# OpenPMU_BBB_Cape_V2_3.net
KiCad netlist of a schematic drawn in EAGLE
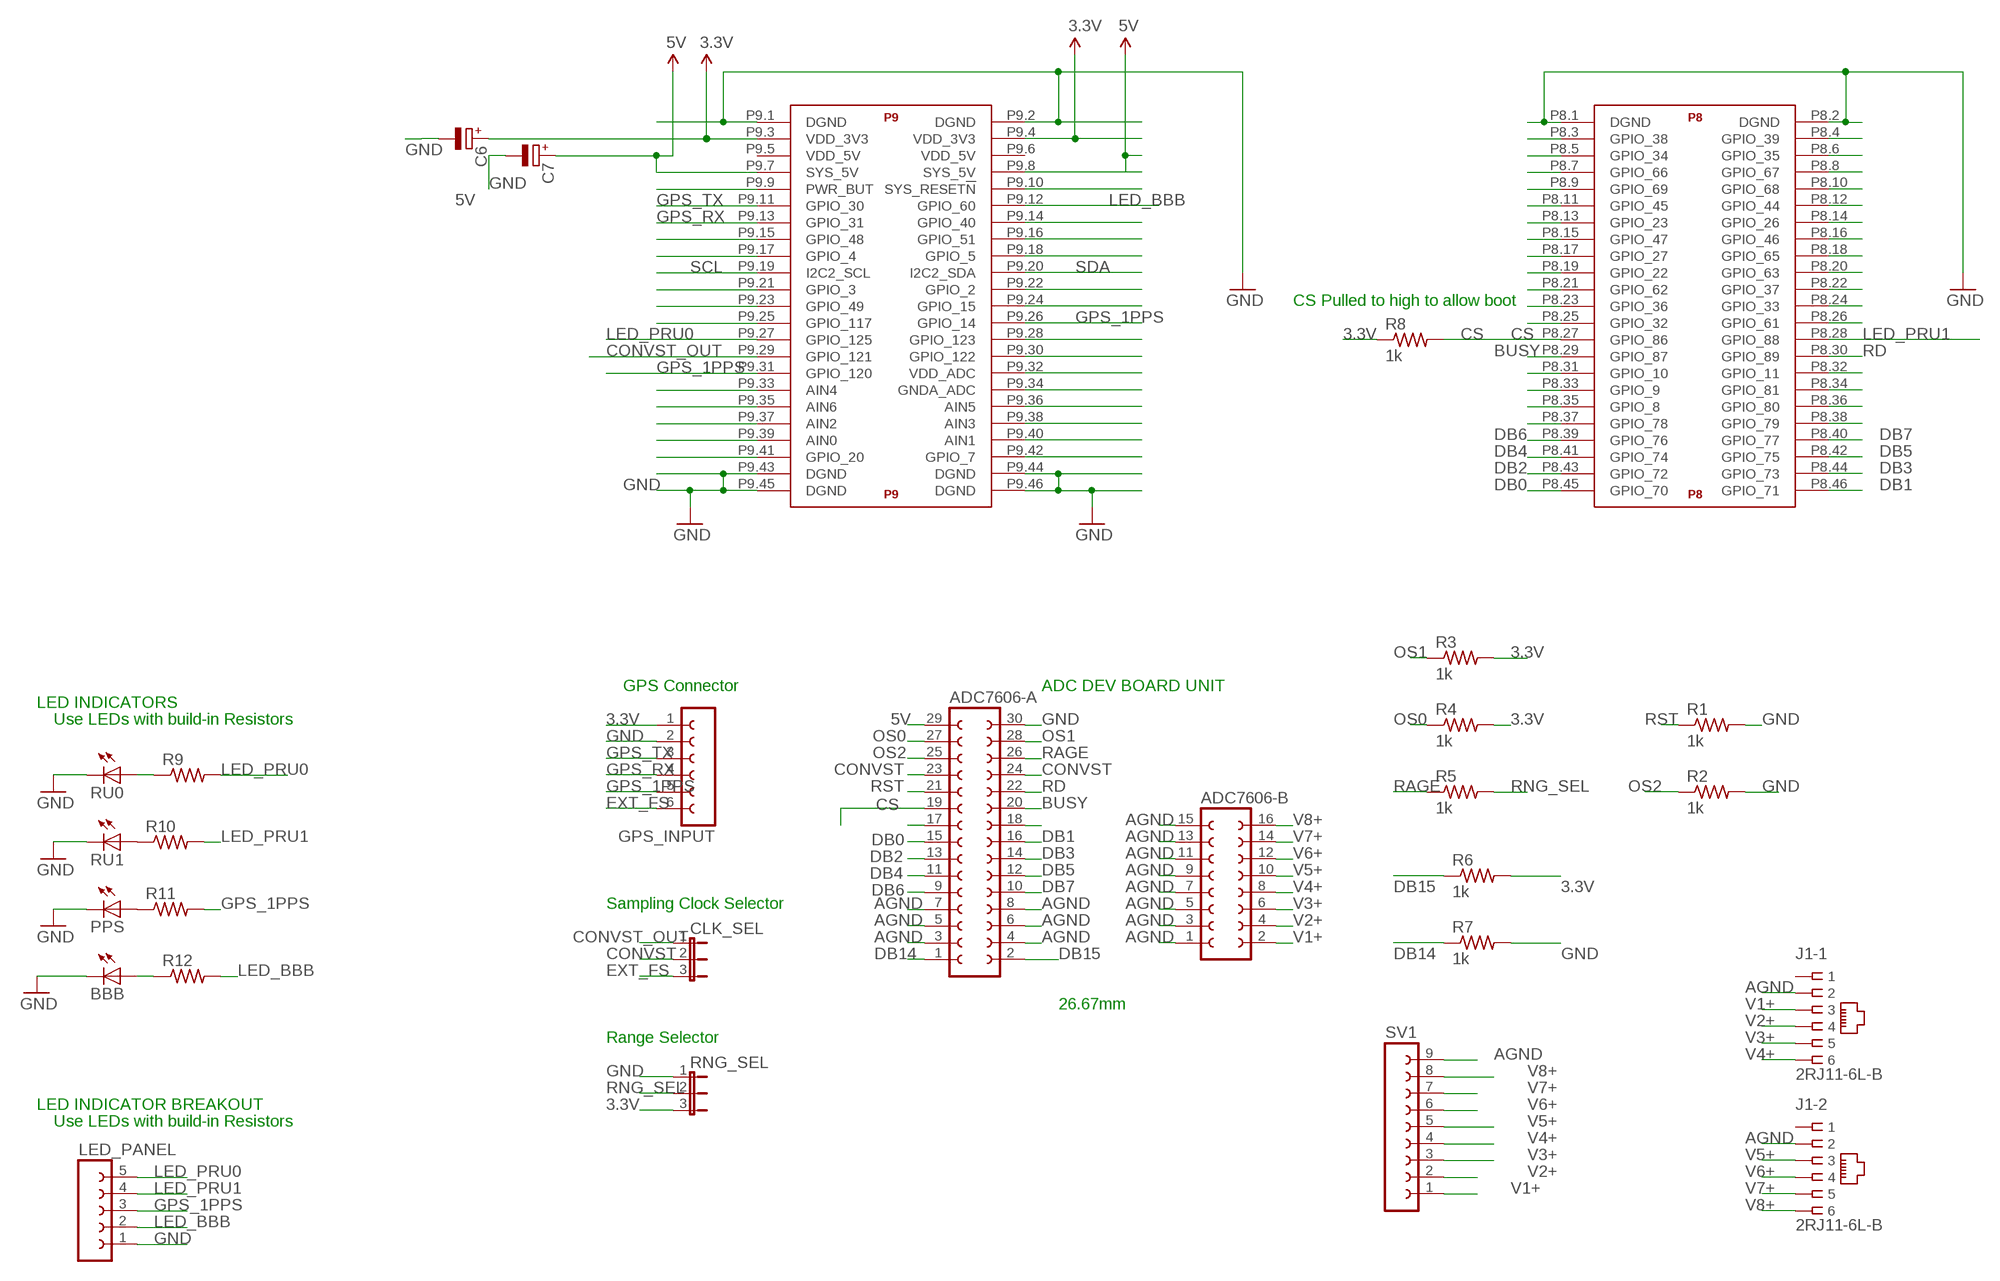
[diagram p0: schematic, sheet 1]

(export (version "E")
  (design (tool "Eeschema 10.0.6"))
  (components
    (comp (ref "ADC7606-A")
      (value "FE15-2")
      (footprint "eagle-import:FE15-2")
      (libsource (lib "eagle-import") (part "FE15-2"))
    )
    (comp (ref "ADC7606-B")
      (value "FE08-2")
      (footprint "eagle-import:FE08-2")
      (libsource (lib "eagle-import") (part "FE08-2"))
    )
    (comp (ref "BBB")
      (value "LEDCHIPLED_1206")
      (footprint "eagle-import:CHIPLED_1206")
      (libsource (lib "eagle-import") (part "LEDCHIPLED_1206"))
    )
    (comp (ref "C6")
      (value "CPOL-EUE1.8-4")
      (footprint "eagle-import:E1,8-4")
      (libsource (lib "eagle-import") (part "CPOL-EUE1.8-4"))
    )
    (comp (ref "C7")
      (value "CPOL-EUE1.8-4")
      (footprint "eagle-import:E1,8-4")
      (libsource (lib "eagle-import") (part "CPOL-EUE1.8-4"))
    )
    (comp (ref "CLK_SEL")
      (value "JP2E")
      (footprint "eagle-import:JP2")
      (libsource (lib "eagle-import") (part "JP2E"))
    )
    (comp (ref "GPS_INPUT")
      (value "FE06-1")
      (footprint "eagle-import:FE06")
      (libsource (lib "eagle-import") (part "FE06-1"))
    )
    (comp (ref "J1")
      (value "2RJ11-6L-B")
      (footprint "eagle-import:2RJ11")
      (fields (field (name "MF") "TYCO ELECTRONICS"))
      (libsource (lib "eagle-import") (part "2RJ11-6L-B"))
    )
    (comp (ref "LED_PANEL")
      (value "FE05-1")
      (footprint "eagle-import:FE05-1")
      (libsource (lib "eagle-import") (part "FE05-1"))
    )
    (comp (ref "PPS")
      (value "LEDCHIPLED_1206")
      (footprint "eagle-import:CHIPLED_1206")
      (libsource (lib "eagle-import") (part "LEDCHIPLED_1206"))
    )
    (comp (ref "R1")
      (value "1k")
      (footprint "eagle-import:0204_7")
      (libsource (lib "eagle-import") (part "R-US_0204/7"))
    )
    (comp (ref "R2")
      (value "1k")
      (footprint "eagle-import:0204_7")
      (libsource (lib "eagle-import") (part "R-US_0204/7"))
    )
    (comp (ref "R3")
      (value "1k")
      (footprint "eagle-import:0204_7")
      (libsource (lib "eagle-import") (part "R-US_0204/7"))
    )
    (comp (ref "R4")
      (value "1k")
      (footprint "eagle-import:0204_7")
      (libsource (lib "eagle-import") (part "R-US_0204/7"))
    )
    (comp (ref "R5")
      (value "1k")
      (footprint "eagle-import:0204_7")
      (libsource (lib "eagle-import") (part "R-US_0204/7"))
    )
    (comp (ref "R6")
      (value "1k")
      (footprint "eagle-import:0204_7")
      (libsource (lib "eagle-import") (part "R-US_0204/7"))
    )
    (comp (ref "R7")
      (value "1k")
      (footprint "eagle-import:0204_7")
      (libsource (lib "eagle-import") (part "R-US_0204/7"))
    )
    (comp (ref "R8")
      (value "1k")
      (footprint "eagle-import:0204_7")
      (libsource (lib "eagle-import") (part "R-US_0204/7"))
    )
    (comp (ref "R9")
      (value "R-US_M1206")
      (footprint "eagle-import:M1206")
      (libsource (lib "eagle-import") (part "R-US_M1206"))
    )
    (comp (ref "R10")
      (value "R-US_M1206")
      (footprint "eagle-import:M1206")
      (libsource (lib "eagle-import") (part "R-US_M1206"))
    )
    (comp (ref "R11")
      (value "R-US_M1206")
      (footprint "eagle-import:M1206")
      (libsource (lib "eagle-import") (part "R-US_M1206"))
    )
    (comp (ref "R12")
      (value "R-US_M1206")
      (footprint "eagle-import:M1206")
      (libsource (lib "eagle-import") (part "R-US_M1206"))
    )
    (comp (ref "RNG_SEL")
      (value "JP2E")
      (footprint "eagle-import:JP2")
      (libsource (lib "eagle-import") (part "JP2E"))
    )
    (comp (ref "RU0")
      (value "LEDCHIPLED_1206")
      (footprint "eagle-import:CHIPLED_1206")
      (libsource (lib "eagle-import") (part "LEDCHIPLED_1206"))
    )
    (comp (ref "RU1")
      (value "LEDCHIPLED_1206")
      (footprint "eagle-import:CHIPLED_1206")
      (libsource (lib "eagle-import") (part "LEDCHIPLED_1206"))
    )
    (comp (ref "SV1")
      (value "FE09-1")
      (footprint "eagle-import:FE09")
      (libsource (lib "eagle-import") (part "FE09-1"))
    )
    (comp (ref "U$1")
      (value "BEAGLE_BONE_BLACK_CAPE")
      (footprint "eagle-import:BEAGLE_BONE_BLACK_CAPE")
      (libsource (lib "eagle-import") (part "BEAGLE_BONE_BLACK_CAPE"))
    )
  )
  (nets
    (net (code "1") (name "/AGND") (class "Default")
      (node (ref "ADC7606-A") (pin "3") (pinfunction "3_3") (pintype "passive"))
      (node (ref "ADC7606-A") (pin "4") (pinfunction "4_4") (pintype "passive"))
      (node (ref "ADC7606-A") (pin "5") (pinfunction "5_5") (pintype "passive"))
      (node (ref "ADC7606-A") (pin "6") (pinfunction "6_6") (pintype "passive"))
      (node (ref "ADC7606-A") (pin "7") (pinfunction "7_7") (pintype "passive"))
      (node (ref "ADC7606-A") (pin "8") (pinfunction "8_8") (pintype "passive"))
      (node (ref "ADC7606-B") (pin "1") (pinfunction "1_1") (pintype "passive"))
      (node (ref "ADC7606-B") (pin "11") (pinfunction "11_11") (pintype "passive"))
      (node (ref "ADC7606-B") (pin "13") (pinfunction "13_13") (pintype "passive"))
      (node (ref "ADC7606-B") (pin "15") (pinfunction "15_15") (pintype "passive"))
      (node (ref "ADC7606-B") (pin "3") (pinfunction "3_3") (pintype "passive"))
      (node (ref "ADC7606-B") (pin "5") (pinfunction "5_5") (pintype "passive"))
      (node (ref "ADC7606-B") (pin "7") (pinfunction "7_7") (pintype "passive"))
      (node (ref "ADC7606-B") (pin "9") (pinfunction "9_9") (pintype "passive"))
      (node (ref "J1") (pin "1-2") (pinfunction "2_1-2") (pintype "passive"))
      (node (ref "J1") (pin "2-2") (pinfunction "2_2-2") (pintype "passive"))
      (node (ref "SV1") (pin "9") (pinfunction "9_9") (pintype "passive"))
    )
    (net (code "2") (name "/BUSY") (class "Default")
      (node (ref "ADC7606-A") (pin "20") (pinfunction "20_20") (pintype "passive"))
      (node (ref "U$1") (pin "P8.29") (pinfunction "GPIO_87_P8.29") (pintype "bidirectional"))
    )
    (net (code "3") (name "/CONVST") (class "Default")
      (node (ref "ADC7606-A") (pin "23") (pinfunction "23_23") (pintype "passive"))
      (node (ref "ADC7606-A") (pin "24") (pinfunction "24_24") (pintype "passive"))
      (node (ref "CLK_SEL") (pin "2") (pinfunction "2_2") (pintype "passive"))
    )
    (net (code "4") (name "/CONVST_OUT") (class "Default")
      (node (ref "CLK_SEL") (pin "1") (pinfunction "1_1") (pintype "passive"))
      (node (ref "U$1") (pin "P9.29") (pinfunction "GPIO_121_P9.29") (pintype "bidirectional"))
    )
    (net (code "5") (name "/CS") (class "Default")
      (node (ref "ADC7606-A") (pin "19") (pinfunction "19_19") (pintype "passive"))
      (node (ref "R8") (pin "2") (pinfunction "2_2") (pintype "passive"))
      (node (ref "U$1") (pin "P8.27") (pinfunction "GPIO_86_P8.27") (pintype "bidirectional"))
    )
    (net (code "6") (name "/DB0") (class "Default")
      (node (ref "ADC7606-A") (pin "15") (pinfunction "15_15") (pintype "passive"))
      (node (ref "U$1") (pin "P8.45") (pinfunction "GPIO_70_P8.45") (pintype "bidirectional"))
    )
    (net (code "7") (name "/DB1") (class "Default")
      (node (ref "ADC7606-A") (pin "16") (pinfunction "16_16") (pintype "passive"))
      (node (ref "U$1") (pin "P8.46") (pinfunction "GPIO_71_P8.46") (pintype "bidirectional"))
    )
    (net (code "8") (name "/DB2") (class "Default")
      (node (ref "ADC7606-A") (pin "13") (pinfunction "13_13") (pintype "passive"))
      (node (ref "U$1") (pin "P8.43") (pinfunction "GPIO_72_P8.43") (pintype "bidirectional"))
    )
    (net (code "9") (name "/DB3") (class "Default")
      (node (ref "ADC7606-A") (pin "14") (pinfunction "14_14") (pintype "passive"))
      (node (ref "U$1") (pin "P8.44") (pinfunction "GPIO_73_P8.44") (pintype "bidirectional"))
    )
    (net (code "10") (name "/DB4") (class "Default")
      (node (ref "ADC7606-A") (pin "11") (pinfunction "11_11") (pintype "passive"))
      (node (ref "U$1") (pin "P8.41") (pinfunction "GPIO_74_P8.41") (pintype "bidirectional"))
    )
    (net (code "11") (name "/DB5") (class "Default")
      (node (ref "ADC7606-A") (pin "12") (pinfunction "12_12") (pintype "passive"))
      (node (ref "U$1") (pin "P8.42") (pinfunction "GPIO_75_P8.42") (pintype "bidirectional"))
    )
    (net (code "12") (name "/DB6") (class "Default")
      (node (ref "ADC7606-A") (pin "9") (pinfunction "9_9") (pintype "passive"))
      (node (ref "U$1") (pin "P8.39") (pinfunction "GPIO_76_P8.39") (pintype "bidirectional"))
    )
    (net (code "13") (name "/DB7") (class "Default")
      (node (ref "ADC7606-A") (pin "10") (pinfunction "10_10") (pintype "passive"))
      (node (ref "U$1") (pin "P8.40") (pinfunction "GPIO_77_P8.40") (pintype "bidirectional"))
    )
    (net (code "14") (name "/DB14") (class "Default")
      (node (ref "ADC7606-A") (pin "1") (pinfunction "1_1") (pintype "passive"))
      (node (ref "R7") (pin "1") (pinfunction "1_1") (pintype "passive"))
    )
    (net (code "15") (name "/DB15") (class "Default")
      (node (ref "ADC7606-A") (pin "2") (pinfunction "2_2") (pintype "passive"))
      (node (ref "R6") (pin "1") (pinfunction "1_1") (pintype "passive"))
    )
    (net (code "16") (name "/EXT_FS") (class "Default")
      (node (ref "CLK_SEL") (pin "3") (pinfunction "3_3") (pintype "passive"))
      (node (ref "GPS_INPUT") (pin "6") (pinfunction "6_6") (pintype "passive"))
    )
    (net (code "17") (name "/GPS_1PPS") (class "Default")
      (node (ref "GPS_INPUT") (pin "5") (pinfunction "5_5") (pintype "passive"))
      (node (ref "LED_PANEL") (pin "3") (pinfunction "3_3") (pintype "passive"))
      (node (ref "R11") (pin "2") (pinfunction "2_2") (pintype "passive"))
      (node (ref "U$1") (pin "P9.26") (pinfunction "GPIO_14_P9.26") (pintype "bidirectional"))
      (node (ref "U$1") (pin "P9.31") (pinfunction "GPIO_120_P9.31") (pintype "bidirectional"))
    )
    (net (code "18") (name "/GPS_RX") (class "Default")
      (node (ref "GPS_INPUT") (pin "4") (pinfunction "4_4") (pintype "passive"))
      (node (ref "U$1") (pin "P9.13") (pinfunction "GPIO_31_P9.13") (pintype "bidirectional"))
    )
    (net (code "19") (name "/GPS_TX") (class "Default")
      (node (ref "GPS_INPUT") (pin "3") (pinfunction "3_3") (pintype "passive"))
      (node (ref "U$1") (pin "P9.11") (pinfunction "GPIO_30_P9.11") (pintype "bidirectional"))
    )
    (net (code "20") (name "/LED_BBB") (class "Default")
      (node (ref "LED_PANEL") (pin "2") (pinfunction "2_2") (pintype "passive"))
      (node (ref "R12") (pin "2") (pinfunction "2_2") (pintype "passive"))
      (node (ref "U$1") (pin "P9.12") (pinfunction "GPIO_60_P9.12") (pintype "bidirectional"))
    )
    (net (code "21") (name "/LED_PRU0") (class "Default")
      (node (ref "LED_PANEL") (pin "5") (pinfunction "5_5") (pintype "passive"))
      (node (ref "R9") (pin "2") (pinfunction "2_2") (pintype "passive"))
      (node (ref "U$1") (pin "P9.27") (pinfunction "GPIO_125_P9.27") (pintype "bidirectional"))
    )
    (net (code "22") (name "/LED_PRU1") (class "Default")
      (node (ref "LED_PANEL") (pin "4") (pinfunction "4_4") (pintype "passive"))
      (node (ref "R10") (pin "2") (pinfunction "2_2") (pintype "passive"))
      (node (ref "U$1") (pin "P8.28") (pinfunction "GPIO_88_P8.28") (pintype "bidirectional"))
    )
    (net (code "23") (name "/OS0") (class "Default")
      (node (ref "ADC7606-A") (pin "27") (pinfunction "27_27") (pintype "passive"))
      (node (ref "R4") (pin "1") (pinfunction "1_1") (pintype "passive"))
    )
    (net (code "24") (name "/OS1") (class "Default")
      (node (ref "ADC7606-A") (pin "28") (pinfunction "28_28") (pintype "passive"))
      (node (ref "R3") (pin "1") (pinfunction "1_1") (pintype "passive"))
    )
    (net (code "25") (name "/OS2") (class "Default")
      (node (ref "ADC7606-A") (pin "25") (pinfunction "25_25") (pintype "passive"))
      (node (ref "R2") (pin "1") (pinfunction "1_1") (pintype "passive"))
    )
    (net (code "26") (name "/RAGE") (class "Default")
      (node (ref "ADC7606-A") (pin "26") (pinfunction "26_26") (pintype "passive"))
      (node (ref "R5") (pin "1") (pinfunction "1_1") (pintype "passive"))
    )
    (net (code "27") (name "/RD") (class "Default")
      (node (ref "ADC7606-A") (pin "22") (pinfunction "22_22") (pintype "passive"))
      (node (ref "U$1") (pin "P8.30") (pinfunction "GPIO_89_P8.30") (pintype "bidirectional"))
    )
    (net (code "28") (name "/RNG_SEL") (class "Default")
      (node (ref "R5") (pin "2") (pinfunction "2_2") (pintype "passive"))
      (node (ref "RNG_SEL") (pin "2") (pinfunction "2_2") (pintype "passive"))
    )
    (net (code "29") (name "/RST") (class "Default")
      (node (ref "ADC7606-A") (pin "21") (pinfunction "21_21") (pintype "passive"))
      (node (ref "R1") (pin "1") (pinfunction "1_1") (pintype "passive"))
    )
    (net (code "30") (name "/SCL") (class "Default")
      (node (ref "U$1") (pin "P9.19") (pinfunction "I2C2_SCL_P9.19") (pintype "bidirectional"))
    )
    (net (code "31") (name "/SDA") (class "Default")
      (node (ref "U$1") (pin "P9.20") (pinfunction "I2C2_SDA_P9.20") (pintype "bidirectional"))
    )
    (net (code "32") (name "/V1+") (class "Default")
      (node (ref "ADC7606-B") (pin "2") (pinfunction "2_2") (pintype "passive"))
      (node (ref "J1") (pin "1-3") (pinfunction "3_1-3") (pintype "passive"))
      (node (ref "SV1") (pin "1") (pinfunction "1_1") (pintype "passive"))
    )
    (net (code "33") (name "/V2+") (class "Default")
      (node (ref "ADC7606-B") (pin "4") (pinfunction "4_4") (pintype "passive"))
      (node (ref "J1") (pin "1-4") (pinfunction "4_1-4") (pintype "passive"))
      (node (ref "SV1") (pin "2") (pinfunction "2_2") (pintype "passive"))
    )
    (net (code "34") (name "/V3+") (class "Default")
      (node (ref "ADC7606-B") (pin "6") (pinfunction "6_6") (pintype "passive"))
      (node (ref "J1") (pin "1-5") (pinfunction "5_1-5") (pintype "passive"))
      (node (ref "SV1") (pin "3") (pinfunction "3_3") (pintype "passive"))
    )
    (net (code "35") (name "/V4+") (class "Default")
      (node (ref "ADC7606-B") (pin "8") (pinfunction "8_8") (pintype "passive"))
      (node (ref "J1") (pin "1-6") (pinfunction "6_1-6") (pintype "passive"))
      (node (ref "SV1") (pin "4") (pinfunction "4_4") (pintype "passive"))
    )
    (net (code "36") (name "/V5+") (class "Default")
      (node (ref "ADC7606-B") (pin "10") (pinfunction "10_10") (pintype "passive"))
      (node (ref "J1") (pin "2-3") (pinfunction "3_2-3") (pintype "passive"))
      (node (ref "SV1") (pin "5") (pinfunction "5_5") (pintype "passive"))
    )
    (net (code "37") (name "/V6+") (class "Default")
      (node (ref "ADC7606-B") (pin "12") (pinfunction "12_12") (pintype "passive"))
      (node (ref "J1") (pin "2-4") (pinfunction "4_2-4") (pintype "passive"))
      (node (ref "SV1") (pin "6") (pinfunction "6_6") (pintype "passive"))
    )
    (net (code "38") (name "/V7+") (class "Default")
      (node (ref "ADC7606-B") (pin "14") (pinfunction "14_14") (pintype "passive"))
      (node (ref "J1") (pin "2-5") (pinfunction "5_2-5") (pintype "passive"))
      (node (ref "SV1") (pin "7") (pinfunction "7_7") (pintype "passive"))
    )
    (net (code "39") (name "/V8+") (class "Default")
      (node (ref "ADC7606-B") (pin "16") (pinfunction "16_16") (pintype "passive"))
      (node (ref "J1") (pin "2-6") (pinfunction "6_2-6") (pintype "passive"))
      (node (ref "SV1") (pin "8") (pinfunction "8_8") (pintype "passive"))
    )
    (net (code "40") (name "3.3V") (class "Default")
      (node (ref "C6") (pin "+") (pinfunction "+_+") (pintype "passive"))
      (node (ref "GPS_INPUT") (pin "1") (pinfunction "1_1") (pintype "passive"))
      (node (ref "R3") (pin "2") (pinfunction "2_2") (pintype "passive"))
      (node (ref "R4") (pin "2") (pinfunction "2_2") (pintype "passive"))
      (node (ref "R6") (pin "2") (pinfunction "2_2") (pintype "passive"))
      (node (ref "R8") (pin "1") (pinfunction "1_1") (pintype "passive"))
      (node (ref "RNG_SEL") (pin "3") (pinfunction "3_3") (pintype "passive"))
      (node (ref "U$1") (pin "P9.3") (pinfunction "VDD_3V3_P9.3") (pintype "bidirectional"))
      (node (ref "U$1") (pin "P9.4") (pinfunction "VDD_3V3_P9.4") (pintype "bidirectional"))
    )
    (net (code "41") (name "5V") (class "Default")
      (node (ref "ADC7606-A") (pin "29") (pinfunction "29_29") (pintype "passive"))
      (node (ref "C7") (pin "+") (pinfunction "+_+") (pintype "passive"))
      (node (ref "U$1") (pin "P9.7") (pinfunction "SYS_5V_P9.7") (pintype "bidirectional"))
      (node (ref "U$1") (pin "P9.8") (pinfunction "SYS_5V_P9.8") (pintype "bidirectional"))
    )
    (net (code "42") (name "GND") (class "Default")
      (node (ref "ADC7606-A") (pin "30") (pinfunction "30_30") (pintype "passive"))
      (node (ref "BBB") (pin "C") (pinfunction "C_C") (pintype "passive"))
      (node (ref "C6") (pin "-") (pinfunction "-_-") (pintype "passive"))
      (node (ref "C7") (pin "-") (pinfunction "-_-") (pintype "passive"))
      (node (ref "GPS_INPUT") (pin "2") (pinfunction "2_2") (pintype "passive"))
      (node (ref "LED_PANEL") (pin "1") (pinfunction "1_1") (pintype "passive"))
      (node (ref "PPS") (pin "C") (pinfunction "C_C") (pintype "passive"))
      (node (ref "R1") (pin "2") (pinfunction "2_2") (pintype "passive"))
      (node (ref "R2") (pin "2") (pinfunction "2_2") (pintype "passive"))
      (node (ref "R7") (pin "2") (pinfunction "2_2") (pintype "passive"))
      (node (ref "RNG_SEL") (pin "1") (pinfunction "1_1") (pintype "passive"))
      (node (ref "RU0") (pin "C") (pinfunction "C_C") (pintype "passive"))
      (node (ref "RU1") (pin "C") (pinfunction "C_C") (pintype "passive"))
      (node (ref "U$1") (pin "P8.1") (pinfunction "DGND_P8.1") (pintype "bidirectional"))
      (node (ref "U$1") (pin "P8.2") (pinfunction "DGND_P8.2") (pintype "bidirectional"))
      (node (ref "U$1") (pin "P9.1") (pinfunction "DGND_P9.1") (pintype "bidirectional"))
      (node (ref "U$1") (pin "P9.2") (pinfunction "DGND_P9.2") (pintype "bidirectional"))
      (node (ref "U$1") (pin "P9.43") (pinfunction "DGND_P9.43") (pintype "bidirectional"))
      (node (ref "U$1") (pin "P9.44") (pinfunction "DGND_P9.44") (pintype "bidirectional"))
      (node (ref "U$1") (pin "P9.45") (pinfunction "DGND_P9.45") (pintype "bidirectional"))
      (node (ref "U$1") (pin "P9.46") (pinfunction "DGND_P9.46") (pintype "bidirectional"))
    )
    (net (code "43") (name "Net-(BBB-PadA)") (class "Default")
      (node (ref "BBB") (pin "A") (pinfunction "A_A") (pintype "passive"))
      (node (ref "R12") (pin "1") (pinfunction "1_1") (pintype "passive"))
    )
    (net (code "44") (name "Net-(PPS-PadA)") (class "Default")
      (node (ref "PPS") (pin "A") (pinfunction "A_A") (pintype "passive"))
      (node (ref "R11") (pin "1") (pinfunction "1_1") (pintype "passive"))
    )
    (net (code "45") (name "Net-(R9-Pad1)") (class "Default")
      (node (ref "R9") (pin "1") (pinfunction "1_1") (pintype "passive"))
      (node (ref "RU0") (pin "A") (pinfunction "A_A") (pintype "passive"))
    )
    (net (code "46") (name "Net-(R10-Pad1)") (class "Default")
      (node (ref "R10") (pin "1") (pinfunction "1_1") (pintype "passive"))
      (node (ref "RU1") (pin "A") (pinfunction "A_A") (pintype "passive"))
    )
    (net (code "47") (name "unconnected-(ADC7606-A-Pad17)") (class "Default")
      (node (ref "ADC7606-A") (pin "17") (pinfunction "17_17") (pintype "passive"))
    )
    (net (code "48") (name "unconnected-(ADC7606-A-Pad18)") (class "Default")
      (node (ref "ADC7606-A") (pin "18") (pinfunction "18_18") (pintype "passive"))
    )
    (net (code "49") (name "unconnected-(J1A-1-Pad1-1)") (class "Default")
      (node (ref "J1") (pin "1-1") (pinfunction "1_1-1") (pintype "passive"))
    )
    (net (code "50") (name "unconnected-(J1B-1-Pad2-1)") (class "Default")
      (node (ref "J1") (pin "2-1") (pinfunction "1_2-1") (pintype "passive"))
    )
    (net (code "51") (name "unconnected-(U$1A-GPIO_8-PadP8.35)") (class "Default")
      (node (ref "U$1") (pin "P8.35") (pinfunction "GPIO_8_P8.35") (pintype "bidirectional"))
    )
    (net (code "52") (name "unconnected-(U$1A-GPIO_9-PadP8.33)") (class "Default")
      (node (ref "U$1") (pin "P8.33") (pinfunction "GPIO_9_P8.33") (pintype "bidirectional"))
    )
    (net (code "53") (name "unconnected-(U$1A-GPIO_10-PadP8.31)") (class "Default")
      (node (ref "U$1") (pin "P8.31") (pinfunction "GPIO_10_P8.31") (pintype "bidirectional"))
    )
    (net (code "54") (name "unconnected-(U$1A-GPIO_11-PadP8.32)") (class "Default")
      (node (ref "U$1") (pin "P8.32") (pinfunction "GPIO_11_P8.32") (pintype "bidirectional"))
    )
    (net (code "55") (name "unconnected-(U$1A-GPIO_22-PadP8.19)") (class "Default")
      (node (ref "U$1") (pin "P8.19") (pinfunction "GPIO_22_P8.19") (pintype "bidirectional"))
    )
    (net (code "56") (name "unconnected-(U$1A-GPIO_23-PadP8.13)") (class "Default")
      (node (ref "U$1") (pin "P8.13") (pinfunction "GPIO_23_P8.13") (pintype "bidirectional"))
    )
    (net (code "57") (name "unconnected-(U$1A-GPIO_26-PadP8.14)") (class "Default")
      (node (ref "U$1") (pin "P8.14") (pinfunction "GPIO_26_P8.14") (pintype "bidirectional"))
    )
    (net (code "58") (name "unconnected-(U$1A-GPIO_27-PadP8.17)") (class "Default")
      (node (ref "U$1") (pin "P8.17") (pinfunction "GPIO_27_P8.17") (pintype "bidirectional"))
    )
    (net (code "59") (name "unconnected-(U$1A-GPIO_32-PadP8.25)") (class "Default")
      (node (ref "U$1") (pin "P8.25") (pinfunction "GPIO_32_P8.25") (pintype "bidirectional"))
    )
    (net (code "60") (name "unconnected-(U$1A-GPIO_33-PadP8.24)") (class "Default")
      (node (ref "U$1") (pin "P8.24") (pinfunction "GPIO_33_P8.24") (pintype "bidirectional"))
    )
    (net (code "61") (name "unconnected-(U$1A-GPIO_34-PadP8.5)") (class "Default")
      (node (ref "U$1") (pin "P8.5") (pinfunction "GPIO_34_P8.5") (pintype "bidirectional"))
    )
    (net (code "62") (name "unconnected-(U$1A-GPIO_35-PadP8.6)") (class "Default")
      (node (ref "U$1") (pin "P8.6") (pinfunction "GPIO_35_P8.6") (pintype "bidirectional"))
    )
    (net (code "63") (name "unconnected-(U$1A-GPIO_36-PadP8.23)") (class "Default")
      (node (ref "U$1") (pin "P8.23") (pinfunction "GPIO_36_P8.23") (pintype "bidirectional"))
    )
    (net (code "64") (name "unconnected-(U$1A-GPIO_37-PadP8.22)") (class "Default")
      (node (ref "U$1") (pin "P8.22") (pinfunction "GPIO_37_P8.22") (pintype "bidirectional"))
    )
    (net (code "65") (name "unconnected-(U$1A-GPIO_38-PadP8.3)") (class "Default")
      (node (ref "U$1") (pin "P8.3") (pinfunction "GPIO_38_P8.3") (pintype "bidirectional"))
    )
    (net (code "66") (name "unconnected-(U$1A-GPIO_39-PadP8.4)") (class "Default")
      (node (ref "U$1") (pin "P8.4") (pinfunction "GPIO_39_P8.4") (pintype "bidirectional"))
    )
    (net (code "67") (name "unconnected-(U$1A-GPIO_44-PadP8.12)") (class "Default")
      (node (ref "U$1") (pin "P8.12") (pinfunction "GPIO_44_P8.12") (pintype "bidirectional"))
    )
    (net (code "68") (name "unconnected-(U$1A-GPIO_45-PadP8.11)") (class "Default")
      (node (ref "U$1") (pin "P8.11") (pinfunction "GPIO_45_P8.11") (pintype "bidirectional"))
    )
    (net (code "69") (name "unconnected-(U$1A-GPIO_46-PadP8.16)") (class "Default")
      (node (ref "U$1") (pin "P8.16") (pinfunction "GPIO_46_P8.16") (pintype "bidirectional"))
    )
    (net (code "70") (name "unconnected-(U$1A-GPIO_47-PadP8.15)") (class "Default")
      (node (ref "U$1") (pin "P8.15") (pinfunction "GPIO_47_P8.15") (pintype "bidirectional"))
    )
    (net (code "71") (name "unconnected-(U$1A-GPIO_61-PadP8.26)") (class "Default")
      (node (ref "U$1") (pin "P8.26") (pinfunction "GPIO_61_P8.26") (pintype "bidirectional"))
    )
    (net (code "72") (name "unconnected-(U$1A-GPIO_62-PadP8.21)") (class "Default")
      (node (ref "U$1") (pin "P8.21") (pinfunction "GPIO_62_P8.21") (pintype "bidirectional"))
    )
    (net (code "73") (name "unconnected-(U$1A-GPIO_63-PadP8.20)") (class "Default")
      (node (ref "U$1") (pin "P8.20") (pinfunction "GPIO_63_P8.20") (pintype "bidirectional"))
    )
    (net (code "74") (name "unconnected-(U$1A-GPIO_65-PadP8.18)") (class "Default")
      (node (ref "U$1") (pin "P8.18") (pinfunction "GPIO_65_P8.18") (pintype "bidirectional"))
    )
    (net (code "75") (name "unconnected-(U$1A-GPIO_66-PadP8.7)") (class "Default")
      (node (ref "U$1") (pin "P8.7") (pinfunction "GPIO_66_P8.7") (pintype "bidirectional"))
    )
    (net (code "76") (name "unconnected-(U$1A-GPIO_67-PadP8.8)") (class "Default")
      (node (ref "U$1") (pin "P8.8") (pinfunction "GPIO_67_P8.8") (pintype "bidirectional"))
    )
    (net (code "77") (name "unconnected-(U$1A-GPIO_68-PadP8.10)") (class "Default")
      (node (ref "U$1") (pin "P8.10") (pinfunction "GPIO_68_P8.10") (pintype "bidirectional"))
    )
    (net (code "78") (name "unconnected-(U$1A-GPIO_69-PadP8.9)") (class "Default")
      (node (ref "U$1") (pin "P8.9") (pinfunction "GPIO_69_P8.9") (pintype "bidirectional"))
    )
    (net (code "79") (name "unconnected-(U$1A-GPIO_78-PadP8.37)") (class "Default")
      (node (ref "U$1") (pin "P8.37") (pinfunction "GPIO_78_P8.37") (pintype "bidirectional"))
    )
    (net (code "80") (name "unconnected-(U$1A-GPIO_79-PadP8.38)") (class "Default")
      (node (ref "U$1") (pin "P8.38") (pinfunction "GPIO_79_P8.38") (pintype "bidirectional"))
    )
    (net (code "81") (name "unconnected-(U$1A-GPIO_80-PadP8.36)") (class "Default")
      (node (ref "U$1") (pin "P8.36") (pinfunction "GPIO_80_P8.36") (pintype "bidirectional"))
    )
    (net (code "82") (name "unconnected-(U$1A-GPIO_81-PadP8.34)") (class "Default")
      (node (ref "U$1") (pin "P8.34") (pinfunction "GPIO_81_P8.34") (pintype "bidirectional"))
    )
    (net (code "83") (name "unconnected-(U$1B-AIN0-PadP9.39)") (class "Default")
      (node (ref "U$1") (pin "P9.39") (pinfunction "AIN0_P9.39") (pintype "bidirectional"))
    )
    (net (code "84") (name "unconnected-(U$1B-AIN1-PadP9.40)") (class "Default")
      (node (ref "U$1") (pin "P9.40") (pinfunction "AIN1_P9.40") (pintype "bidirectional"))
    )
    (net (code "85") (name "unconnected-(U$1B-AIN2-PadP9.37)") (class "Default")
      (node (ref "U$1") (pin "P9.37") (pinfunction "AIN2_P9.37") (pintype "bidirectional"))
    )
    (net (code "86") (name "unconnected-(U$1B-AIN3-PadP9.38)") (class "Default")
      (node (ref "U$1") (pin "P9.38") (pinfunction "AIN3_P9.38") (pintype "bidirectional"))
    )
    (net (code "87") (name "unconnected-(U$1B-AIN4-PadP9.33)") (class "Default")
      (node (ref "U$1") (pin "P9.33") (pinfunction "AIN4_P9.33") (pintype "bidirectional"))
    )
    (net (code "88") (name "unconnected-(U$1B-AIN5-PadP9.36)") (class "Default")
      (node (ref "U$1") (pin "P9.36") (pinfunction "AIN5_P9.36") (pintype "bidirectional"))
    )
    (net (code "89") (name "unconnected-(U$1B-AIN6-PadP9.35)") (class "Default")
      (node (ref "U$1") (pin "P9.35") (pinfunction "AIN6_P9.35") (pintype "bidirectional"))
    )
    (net (code "90") (name "unconnected-(U$1B-GNDA_ADC-PadP9.34)") (class "Default")
      (node (ref "U$1") (pin "P9.34") (pinfunction "GNDA_ADC_P9.34") (pintype "bidirectional"))
    )
    (net (code "91") (name "unconnected-(U$1B-GPIO_2-PadP9.22)") (class "Default")
      (node (ref "U$1") (pin "P9.22") (pinfunction "GPIO_2_P9.22") (pintype "bidirectional"))
    )
    (net (code "92") (name "unconnected-(U$1B-GPIO_3-PadP9.21)") (class "Default")
      (node (ref "U$1") (pin "P9.21") (pinfunction "GPIO_3_P9.21") (pintype "bidirectional"))
    )
    (net (code "93") (name "unconnected-(U$1B-GPIO_4-PadP9.17)") (class "Default")
      (node (ref "U$1") (pin "P9.17") (pinfunction "GPIO_4_P9.17") (pintype "bidirectional"))
    )
    (net (code "94") (name "unconnected-(U$1B-GPIO_5-PadP9.18)") (class "Default")
      (node (ref "U$1") (pin "P9.18") (pinfunction "GPIO_5_P9.18") (pintype "bidirectional"))
    )
    (net (code "95") (name "unconnected-(U$1B-GPIO_7-PadP9.42)") (class "Default")
      (node (ref "U$1") (pin "P9.42") (pinfunction "GPIO_7_P9.42") (pintype "bidirectional"))
    )
    (net (code "96") (name "unconnected-(U$1B-GPIO_15-PadP9.24)") (class "Default")
      (node (ref "U$1") (pin "P9.24") (pinfunction "GPIO_15_P9.24") (pintype "bidirectional"))
    )
    (net (code "97") (name "unconnected-(U$1B-GPIO_20-PadP9.41)") (class "Default")
      (node (ref "U$1") (pin "P9.41") (pinfunction "GPIO_20_P9.41") (pintype "bidirectional"))
    )
    (net (code "98") (name "unconnected-(U$1B-GPIO_40-PadP9.14)") (class "Default")
      (node (ref "U$1") (pin "P9.14") (pinfunction "GPIO_40_P9.14") (pintype "bidirectional"))
    )
    (net (code "99") (name "unconnected-(U$1B-GPIO_48-PadP9.15)") (class "Default")
      (node (ref "U$1") (pin "P9.15") (pinfunction "GPIO_48_P9.15") (pintype "bidirectional"))
    )
    (net (code "100") (name "unconnected-(U$1B-GPIO_49-PadP9.23)") (class "Default")
      (node (ref "U$1") (pin "P9.23") (pinfunction "GPIO_49_P9.23") (pintype "bidirectional"))
    )
    (net (code "101") (name "unconnected-(U$1B-GPIO_51-PadP9.16)") (class "Default")
      (node (ref "U$1") (pin "P9.16") (pinfunction "GPIO_51_P9.16") (pintype "bidirectional"))
    )
    (net (code "102") (name "unconnected-(U$1B-GPIO_117-PadP9.25)") (class "Default")
      (node (ref "U$1") (pin "P9.25") (pinfunction "GPIO_117_P9.25") (pintype "bidirectional"))
    )
    (net (code "103") (name "unconnected-(U$1B-GPIO_122-PadP9.30)") (class "Default")
      (node (ref "U$1") (pin "P9.30") (pinfunction "GPIO_122_P9.30") (pintype "bidirectional"))
    )
    (net (code "104") (name "unconnected-(U$1B-GPIO_123-PadP9.28)") (class "Default")
      (node (ref "U$1") (pin "P9.28") (pinfunction "GPIO_123_P9.28") (pintype "bidirectional"))
    )
    (net (code "105") (name "unconnected-(U$1B-PWR_BUT-PadP9.9)") (class "Default")
      (node (ref "U$1") (pin "P9.9") (pinfunction "PWR_BUT_P9.9") (pintype "bidirectional"))
    )
    (net (code "106") (name "unconnected-(U$1B-SYS_RESET~{N}-PadP9.10)") (class "Default")
      (node (ref "U$1") (pin "P9.10") (pinfunction "SYS_RESET~{N}_P9.10") (pintype "bidirectional"))
    )
    (net (code "107") (name "unconnected-(U$1B-VDD_5V-PadP9.5)") (class "Default")
      (node (ref "U$1") (pin "P9.5") (pinfunction "VDD_5V_P9.5") (pintype "bidirectional"))
    )
    (net (code "108") (name "unconnected-(U$1B-VDD_5V-PadP9.6)") (class "Default")
      (node (ref "U$1") (pin "P9.6") (pinfunction "VDD_5V_P9.6") (pintype "bidirectional"))
    )
    (net (code "109") (name "unconnected-(U$1B-VDD_ADC-PadP9.32)") (class "Default")
      (node (ref "U$1") (pin "P9.32") (pinfunction "VDD_ADC_P9.32") (pintype "bidirectional"))
    )
  )
)
